# RX-Super-Regenerative-2Transistor-Elekto.net
KiCad netlist of a schematic drawn in EAGLE
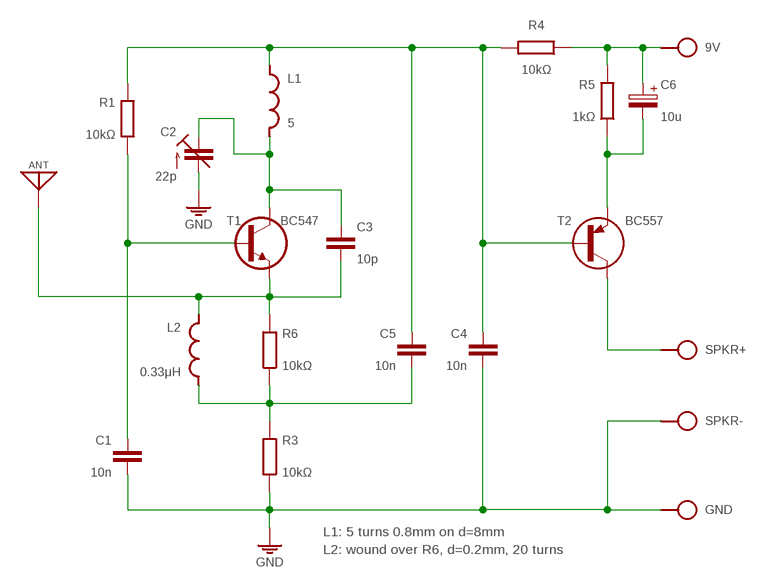
[diagram p0: schematic, sheet 1]

(export (version "E")
  (design (tool "Eeschema 10.0.6"))
  (components
    (comp (ref "9V")
      (value "SPAD")
      (footprint "eagle-import:SPAD")
      (libsource (lib "eagle-import") (part "SPAD"))
    )
    (comp (ref "ANT")
      (value "ANT")
      (footprint "eagle-import:SPAD")
      (libsource (lib "eagle-import") (part "ANT"))
    )
    (comp (ref "C1")
      (value "10n")
      (footprint "eagle-import:C050-020X036")
      (libsource (lib "eagle-import") (part "C050-020X036"))
    )
    (comp (ref "C2")
      (value "22p")
      (footprint "eagle-import:TRIM-2222-808")
      (libsource (lib "eagle-import") (part "C-TR-PH201272222-808-2PINB"))
    )
    (comp (ref "C3")
      (value "10p")
      (footprint "eagle-import:C050-020X036")
      (libsource (lib "eagle-import") (part "C050-020X036"))
    )
    (comp (ref "C4")
      (value "10n")
      (footprint "eagle-import:C050-020X036_V")
      (libsource (lib "eagle-import") (part "C050-020X036/V"))
    )
    (comp (ref "C5")
      (value "10n")
      (footprint "eagle-import:C050-020X036_V")
      (libsource (lib "eagle-import") (part "C050-020X036/V"))
    )
    (comp (ref "C6")
      (value "10u")
      (footprint "eagle-import:E2,5-3")
      (libsource (lib "eagle-import") (part "CPOLE2,5-3"))
    )
    (comp (ref "GND")
      (value "SPAD")
      (footprint "eagle-import:SPAD")
      (libsource (lib "eagle-import") (part "SPAD"))
    )
    (comp (ref "L1")
      (value "5")
      (footprint "eagle-import:L-04_7V-X")
      (libsource (lib "eagle-import") (part "L-SHORTL-04/7V-X"))
    )
    (comp (ref "L2")
      (value "0.33μH")
      (footprint "eagle-import:L-04_7V-X")
      (libsource (lib "eagle-import") (part "L-SHORTL-04/7V-X"))
    )
    (comp (ref "R1")
      (value "10kΩ")
      (footprint "eagle-import:0202_7")
      (libsource (lib "eagle-import") (part "R0202/7"))
    )
    (comp (ref "R3")
      (value "10kΩ")
      (footprint "eagle-import:0202V")
      (libsource (lib "eagle-import") (part "R0202V"))
    )
    (comp (ref "R4")
      (value "10kΩ")
      (footprint "eagle-import:0202_7")
      (libsource (lib "eagle-import") (part "R0202/7"))
    )
    (comp (ref "R5")
      (value "1kΩ")
      (footprint "eagle-import:0202_7-V")
      (libsource (lib "eagle-import") (part "R0202/7-V"))
    )
    (comp (ref "R6")
      (value "10kΩ")
      (footprint "eagle-import:0202_7-V")
      (libsource (lib "eagle-import") (part "R0202/7-V"))
    )
    (comp (ref "SPKR+")
      (value "SPAD")
      (footprint "eagle-import:SPAD")
      (libsource (lib "eagle-import") (part "SPAD"))
    )
    (comp (ref "SPKR-")
      (value "SPAD")
      (footprint "eagle-import:SPAD")
      (libsource (lib "eagle-import") (part "SPAD"))
    )
    (comp (ref "T1")
      (value "BC547")
      (footprint "eagle-import:TO92-CBE")
      (libsource (lib "eagle-import") (part "BC547CBE"))
    )
    (comp (ref "T2")
      (value "BC557")
      (footprint "eagle-import:TO92-CBE-A")
      (libsource (lib "eagle-import") (part "BC557CBE-A"))
    )
  )
  (nets
    (net (code "1") (name "GND") (class "Default")
      (node (ref "C1") (pin "2") (pinfunction "2_2") (pintype "passive"))
      (node (ref "C2") (pin "2") (pinfunction "A_2") (pintype "passive"))
      (node (ref "C4") (pin "2") (pinfunction "2_2") (pintype "passive"))
      (node (ref "GND") (pin "1") (pinfunction "P$1_1") (pintype "bidirectional"))
      (node (ref "R3") (pin "1") (pinfunction "1_1") (pintype "passive"))
      (node (ref "SPKR-") (pin "1") (pinfunction "P$1_1") (pintype "bidirectional"))
    )
    (net (code "2") (name "Net-(9V-P$1)") (class "Default")
      (node (ref "9V") (pin "1") (pinfunction "P$1_1") (pintype "bidirectional"))
      (node (ref "C6") (pin "+") (pinfunction "+_+") (pintype "passive"))
      (node (ref "R4") (pin "1") (pinfunction "1_1") (pintype "passive"))
      (node (ref "R5") (pin "2") (pinfunction "2_2") (pintype "passive"))
    )
    (net (code "3") (name "Net-(ANT-Pad1)") (class "Default")
      (node (ref "ANT") (pin "1") (pinfunction "1_1") (pintype "output"))
      (node (ref "C3") (pin "2") (pinfunction "2_2") (pintype "passive"))
      (node (ref "L2") (pin "2") (pinfunction "2_2") (pintype "passive"))
      (node (ref "R6") (pin "2") (pinfunction "2_2") (pintype "passive"))
      (node (ref "T1") (pin "E") (pinfunction "E_E") (pintype "passive"))
    )
    (net (code "4") (name "Net-(C1-Pad1)") (class "Default")
      (node (ref "C1") (pin "1") (pinfunction "1_1") (pintype "passive"))
      (node (ref "R1") (pin "1") (pinfunction "1_1") (pintype "passive"))
      (node (ref "T1") (pin "B") (pinfunction "B_B") (pintype "passive"))
    )
    (net (code "5") (name "Net-(C2-E)") (class "Default")
      (node (ref "C2") (pin "3") (pinfunction "E_3") (pintype "passive"))
      (node (ref "C3") (pin "1") (pinfunction "1_1") (pintype "passive"))
      (node (ref "L1") (pin "1") (pinfunction "1_1") (pintype "passive"))
      (node (ref "T1") (pin "C") (pinfunction "C_C") (pintype "passive"))
    )
    (net (code "6") (name "Net-(C4-Pad1)") (class "Default")
      (node (ref "C4") (pin "1") (pinfunction "1_1") (pintype "passive"))
      (node (ref "C5") (pin "1") (pinfunction "1_1") (pintype "passive"))
      (node (ref "L1") (pin "2") (pinfunction "2_2") (pintype "passive"))
      (node (ref "R1") (pin "2") (pinfunction "2_2") (pintype "passive"))
      (node (ref "R4") (pin "2") (pinfunction "2_2") (pintype "passive"))
      (node (ref "T2") (pin "B") (pinfunction "B_B") (pintype "passive"))
    )
    (net (code "7") (name "Net-(C5-Pad2)") (class "Default")
      (node (ref "C5") (pin "2") (pinfunction "2_2") (pintype "passive"))
      (node (ref "L2") (pin "1") (pinfunction "1_1") (pintype "passive"))
      (node (ref "R3") (pin "2") (pinfunction "2_2") (pintype "passive"))
      (node (ref "R6") (pin "1") (pinfunction "1_1") (pintype "passive"))
    )
    (net (code "8") (name "Net-(C6-Pad-)") (class "Default")
      (node (ref "C6") (pin "-") (pinfunction "-_-") (pintype "passive"))
      (node (ref "R5") (pin "1") (pinfunction "1_1") (pintype "passive"))
      (node (ref "T2") (pin "E") (pinfunction "E_E") (pintype "passive"))
    )
    (net (code "9") (name "Net-(SPKR+-P$1)") (class "Default")
      (node (ref "SPKR+") (pin "1") (pinfunction "P$1_1") (pintype "bidirectional"))
      (node (ref "T2") (pin "C") (pinfunction "C_C") (pintype "passive"))
    )
  )
)
